# JtagProgCable.net
KiCad netlist of a schematic drawn in Altium Designer
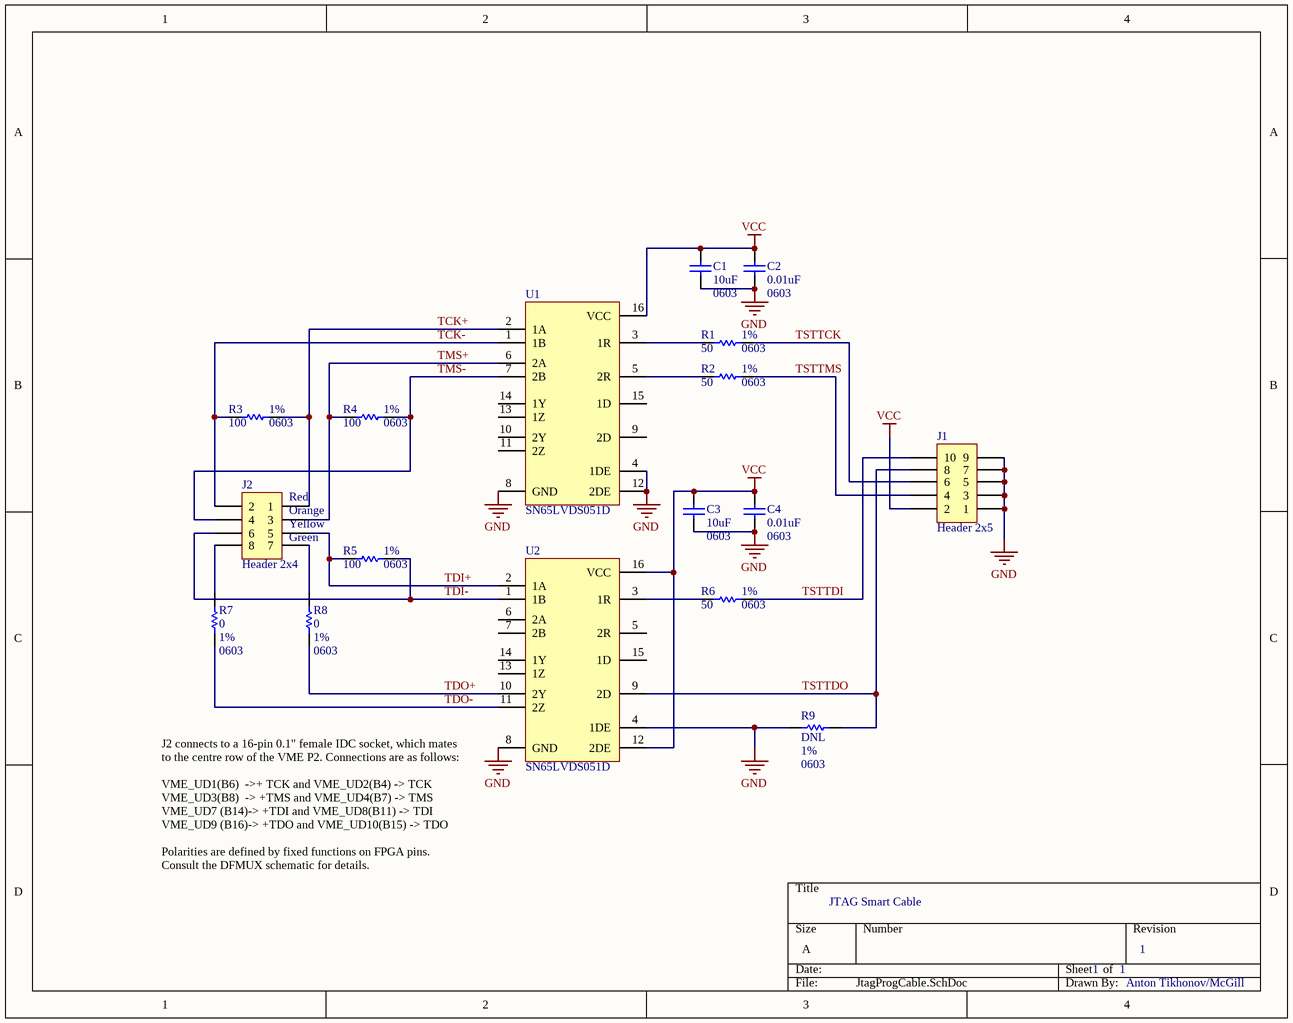
[diagram p0: JtagProgCable.SchDoc]

(export (version "E")
  (design (tool "Eeschema 10.0.6"))
  (components
    (comp (ref "C1")
      (value "10uF")
      (footprint "0603")
      (description "Capacitor, Ceramic, 0603")
      (libsource (lib "Passive_Connectors_Mechanical_Components") (part "Cap1"))
    )
    (comp (ref "C2")
      (value "0.01uF")
      (footprint "0603")
      (description "Capacitor, Ceramic, 0603")
      (libsource (lib "Passive_Connectors_Mechanical_Components") (part "Cap1"))
    )
    (comp (ref "C3")
      (value "10uF")
      (footprint "0603")
      (description "Capacitor, Ceramic, 0603")
      (libsource (lib "Passive_Connectors_Mechanical_Components") (part "Cap1"))
    )
    (comp (ref "C4")
      (value "0.01uF")
      (footprint "0603")
      (description "Capacitor, Ceramic, 0603")
      (libsource (lib "Passive_Connectors_Mechanical_Components") (part "Cap1"))
    )
    (comp (ref "J1")
      (value "Header 2x5")
      (footprint "HDR2X5")
      (description "Header, 0.1\" 5x2-Pin straight")
      (fields (field (name "PUBLISHER") "*"))
      (libsource (lib "Passive_Connectors_Mechanical_Components") (part "Header 2x5"))
    )
    (comp (ref "J2")
      (value "Header 2x4")
      (footprint "HDR2X4")
      (description "Header, 0.1\" 4x2-Pin straight")
      (fields (field (name "PUBLISHER") "*"))
      (libsource (lib "Passive_Connectors_Mechanical_Components") (part "Header 2x4"))
    )
    (comp (ref "R1")
      (value "50")
      (footprint "0603")
      (description "Resistor, 1%, 100ppm, 0603")
      (fields (field (name "PARAM") "1%"))
      (libsource (lib "Passive_Connectors_Mechanical_Components") (part "Res1"))
    )
    (comp (ref "R2")
      (value "50")
      (footprint "0603")
      (description "Resistor, 1%, 100ppm, 0603")
      (fields (field (name "PARAM") "1%"))
      (libsource (lib "Passive_Connectors_Mechanical_Components") (part "Res1"))
    )
    (comp (ref "R3")
      (value "100")
      (footprint "0603")
      (description "Resistor, 1%, 100ppm, 0603")
      (fields (field (name "PARAM") "1%"))
      (libsource (lib "Passive_Connectors_Mechanical_Components") (part "Res1"))
    )
    (comp (ref "R4")
      (value "100")
      (footprint "0603")
      (description "Resistor, 1%, 100ppm, 0603")
      (fields (field (name "PARAM") "1%"))
      (libsource (lib "Passive_Connectors_Mechanical_Components") (part "Res1"))
    )
    (comp (ref "R5")
      (value "100")
      (footprint "0603")
      (description "Resistor, 1%, 100ppm, 0603")
      (fields (field (name "PARAM") "1%"))
      (libsource (lib "Passive_Connectors_Mechanical_Components") (part "Res1"))
    )
    (comp (ref "R6")
      (value "50")
      (footprint "0603")
      (description "Resistor, 1%, 100ppm, 0603")
      (fields (field (name "PARAM") "1%"))
      (libsource (lib "Passive_Connectors_Mechanical_Components") (part "Res1"))
    )
    (comp (ref "R7")
      (value "0")
      (footprint "0603")
      (description "Resistor, 1%, 100ppm, 0603")
      (fields (field (name "PARAM") "1%"))
      (libsource (lib "Passive_Connectors_Mechanical_Components") (part "Res1"))
    )
    (comp (ref "R8")
      (value "0")
      (footprint "0603")
      (description "Resistor, 1%, 100ppm, 0603")
      (fields (field (name "PARAM") "1%"))
      (libsource (lib "Passive_Connectors_Mechanical_Components") (part "Res1"))
    )
    (comp (ref "R9")
      (value "DNL")
      (footprint "0603")
      (description "Resistor, 1%, 100ppm, 0603")
      (fields (field (name "PARAM") "1%"))
      (libsource (lib "Passive_Connectors_Mechanical_Components") (part "Res1"))
    )
    (comp (ref "U1")
      (value "SN65LVDS051D")
      (footprint "SO-G16 (SOIC)")
      (description "differential line drivers and receivers")
      (libsource (lib "Semiconductor_Active_Components") (part "SN65LVDM051QDQ1"))
    )
    (comp (ref "U2")
      (value "SN65LVDS051D")
      (footprint "SO-G16 (SOIC)")
      (description "differential line drivers and receivers")
      (libsource (lib "Semiconductor_Active_Components") (part "SN65LVDM051QDQ1"))
    )
  )
  (nets
    (net (code "1") (name "/TCK+") (class "Default")
      (node (ref "J2") (pin "1") (pinfunction "1_1") (pintype "passive"))
      (node (ref "R3") (pin "2") (pinfunction "2_2") (pintype "passive"))
      (node (ref "U1") (pin "2") (pinfunction "1A_2") (pintype "passive"))
    )
    (net (code "2") (name "/TCK-") (class "Default")
      (node (ref "J2") (pin "2") (pinfunction "2_2") (pintype "passive"))
      (node (ref "R3") (pin "1") (pinfunction "1_1") (pintype "passive"))
      (node (ref "U1") (pin "1") (pinfunction "1B_1") (pintype "passive"))
    )
    (net (code "3") (name "/TDI+") (class "Default")
      (node (ref "J2") (pin "5") (pinfunction "5_5") (pintype "passive"))
      (node (ref "R5") (pin "1") (pinfunction "1_1") (pintype "passive"))
      (node (ref "U2") (pin "2") (pinfunction "1A_2") (pintype "passive"))
    )
    (net (code "4") (name "/TDI-") (class "Default")
      (node (ref "J2") (pin "6") (pinfunction "6_6") (pintype "passive"))
      (node (ref "R5") (pin "2") (pinfunction "2_2") (pintype "passive"))
      (node (ref "U2") (pin "1") (pinfunction "1B_1") (pintype "passive"))
    )
    (net (code "5") (name "/TDO+") (class "Default")
      (node (ref "R8") (pin "1") (pinfunction "1_1") (pintype "passive"))
      (node (ref "U2") (pin "10") (pinfunction "2Y_10") (pintype "passive"))
    )
    (net (code "6") (name "/TDO-") (class "Default")
      (node (ref "R7") (pin "1") (pinfunction "1_1") (pintype "passive"))
      (node (ref "U2") (pin "11") (pinfunction "2Z_11") (pintype "passive"))
    )
    (net (code "7") (name "/TMS+") (class "Default")
      (node (ref "J2") (pin "3") (pinfunction "3_3") (pintype "passive"))
      (node (ref "R4") (pin "1") (pinfunction "1_1") (pintype "passive"))
      (node (ref "U1") (pin "6") (pinfunction "2A_6") (pintype "passive"))
    )
    (net (code "8") (name "/TMS-") (class "Default")
      (node (ref "J2") (pin "4") (pinfunction "4_4") (pintype "passive"))
      (node (ref "R4") (pin "2") (pinfunction "2_2") (pintype "passive"))
      (node (ref "U1") (pin "7") (pinfunction "2B_7") (pintype "passive"))
    )
    (net (code "9") (name "/TSTTCK") (class "Default")
      (node (ref "J1") (pin "6") (pinfunction "6_6") (pintype "passive"))
      (node (ref "R1") (pin "2") (pinfunction "2_2") (pintype "passive"))
    )
    (net (code "10") (name "/TSTTDI") (class "Default")
      (node (ref "J1") (pin "10") (pinfunction "10_10") (pintype "passive"))
      (node (ref "R6") (pin "2") (pinfunction "2_2") (pintype "passive"))
    )
    (net (code "11") (name "/TSTTDO") (class "Default")
      (node (ref "J1") (pin "8") (pinfunction "8_8") (pintype "passive"))
      (node (ref "R9") (pin "1") (pinfunction "1_1") (pintype "passive"))
      (node (ref "U2") (pin "9") (pinfunction "2D_9") (pintype "passive"))
    )
    (net (code "12") (name "/TSTTMS") (class "Default")
      (node (ref "J1") (pin "4") (pinfunction "4_4") (pintype "passive"))
      (node (ref "R2") (pin "2") (pinfunction "2_2") (pintype "passive"))
    )
    (net (code "13") (name "GND") (class "Default")
      (node (ref "C1") (pin "1") (pinfunction "1_1") (pintype "passive"))
      (node (ref "C2") (pin "1") (pinfunction "1_1") (pintype "passive"))
      (node (ref "C3") (pin "1") (pinfunction "1_1") (pintype "passive"))
      (node (ref "C4") (pin "1") (pinfunction "1_1") (pintype "passive"))
      (node (ref "J1") (pin "1") (pinfunction "1_1") (pintype "passive"))
      (node (ref "J1") (pin "3") (pinfunction "3_3") (pintype "passive"))
      (node (ref "J1") (pin "5") (pinfunction "5_5") (pintype "passive"))
      (node (ref "J1") (pin "7") (pinfunction "7_7") (pintype "passive"))
      (node (ref "J1") (pin "9") (pinfunction "9_9") (pintype "passive"))
      (node (ref "R9") (pin "2") (pinfunction "2_2") (pintype "passive"))
      (node (ref "U1") (pin "12") (pinfunction "2DE_12") (pintype "passive"))
      (node (ref "U1") (pin "4") (pinfunction "1DE_4") (pintype "passive"))
      (node (ref "U1") (pin "8") (pinfunction "GND_8") (pintype "passive"))
      (node (ref "U2") (pin "4") (pinfunction "1DE_4") (pintype "passive"))
      (node (ref "U2") (pin "8") (pinfunction "GND_8") (pintype "passive"))
    )
    (net (code "14") (name "Net-(J2-Pad7)") (class "Default")
      (node (ref "J2") (pin "7") (pinfunction "7_7") (pintype "passive"))
      (node (ref "R8") (pin "2") (pinfunction "2_2") (pintype "passive"))
    )
    (net (code "15") (name "Net-(J2-Pad8)") (class "Default")
      (node (ref "J2") (pin "8") (pinfunction "8_8") (pintype "passive"))
      (node (ref "R7") (pin "2") (pinfunction "2_2") (pintype "passive"))
    )
    (net (code "16") (name "Net-(U1-1R)") (class "Default")
      (node (ref "R1") (pin "1") (pinfunction "1_1") (pintype "passive"))
      (node (ref "U1") (pin "3") (pinfunction "1R_3") (pintype "passive"))
    )
    (net (code "17") (name "Net-(U1-2R)") (class "Default")
      (node (ref "R2") (pin "1") (pinfunction "1_1") (pintype "passive"))
      (node (ref "U1") (pin "5") (pinfunction "2R_5") (pintype "passive"))
    )
    (net (code "18") (name "Net-(U2-1R)") (class "Default")
      (node (ref "R6") (pin "1") (pinfunction "1_1") (pintype "passive"))
      (node (ref "U2") (pin "3") (pinfunction "1R_3") (pintype "passive"))
    )
    (net (code "19") (name "VCC") (class "Default")
      (node (ref "C1") (pin "2") (pinfunction "2_2") (pintype "passive"))
      (node (ref "C2") (pin "2") (pinfunction "2_2") (pintype "passive"))
      (node (ref "C3") (pin "2") (pinfunction "2_2") (pintype "passive"))
      (node (ref "C4") (pin "2") (pinfunction "2_2") (pintype "passive"))
      (node (ref "J1") (pin "2") (pinfunction "2_2") (pintype "passive"))
      (node (ref "U1") (pin "16") (pinfunction "VCC_16") (pintype "passive"))
      (node (ref "U2") (pin "12") (pinfunction "2DE_12") (pintype "passive"))
      (node (ref "U2") (pin "16") (pinfunction "VCC_16") (pintype "passive"))
    )
    (net (code "20") (name "unconnected-(U1-1D-Pad15)") (class "Default")
      (node (ref "U1") (pin "15") (pinfunction "1D_15") (pintype "passive"))
    )
    (net (code "21") (name "unconnected-(U1-1Y-Pad14)") (class "Default")
      (node (ref "U1") (pin "14") (pinfunction "1Y_14") (pintype "passive"))
    )
    (net (code "22") (name "unconnected-(U1-1Z-Pad13)") (class "Default")
      (node (ref "U1") (pin "13") (pinfunction "1Z_13") (pintype "passive"))
    )
    (net (code "23") (name "unconnected-(U1-2D-Pad9)") (class "Default")
      (node (ref "U1") (pin "9") (pinfunction "2D_9") (pintype "passive"))
    )
    (net (code "24") (name "unconnected-(U1-2Y-Pad10)") (class "Default")
      (node (ref "U1") (pin "10") (pinfunction "2Y_10") (pintype "passive"))
    )
    (net (code "25") (name "unconnected-(U1-2Z-Pad11)") (class "Default")
      (node (ref "U1") (pin "11") (pinfunction "2Z_11") (pintype "passive"))
    )
    (net (code "26") (name "unconnected-(U2-1D-Pad15)") (class "Default")
      (node (ref "U2") (pin "15") (pinfunction "1D_15") (pintype "passive"))
    )
    (net (code "27") (name "unconnected-(U2-1Y-Pad14)") (class "Default")
      (node (ref "U2") (pin "14") (pinfunction "1Y_14") (pintype "passive"))
    )
    (net (code "28") (name "unconnected-(U2-1Z-Pad13)") (class "Default")
      (node (ref "U2") (pin "13") (pinfunction "1Z_13") (pintype "passive"))
    )
    (net (code "29") (name "unconnected-(U2-2A-Pad6)") (class "Default")
      (node (ref "U2") (pin "6") (pinfunction "2A_6") (pintype "passive"))
    )
    (net (code "30") (name "unconnected-(U2-2B-Pad7)") (class "Default")
      (node (ref "U2") (pin "7") (pinfunction "2B_7") (pintype "passive"))
    )
    (net (code "31") (name "unconnected-(U2-2R-Pad5)") (class "Default")
      (node (ref "U2") (pin "5") (pinfunction "2R_5") (pintype "passive"))
    )
  )
)
